# BrewDoo.net
KiCad netlist of a schematic drawn in EAGLE
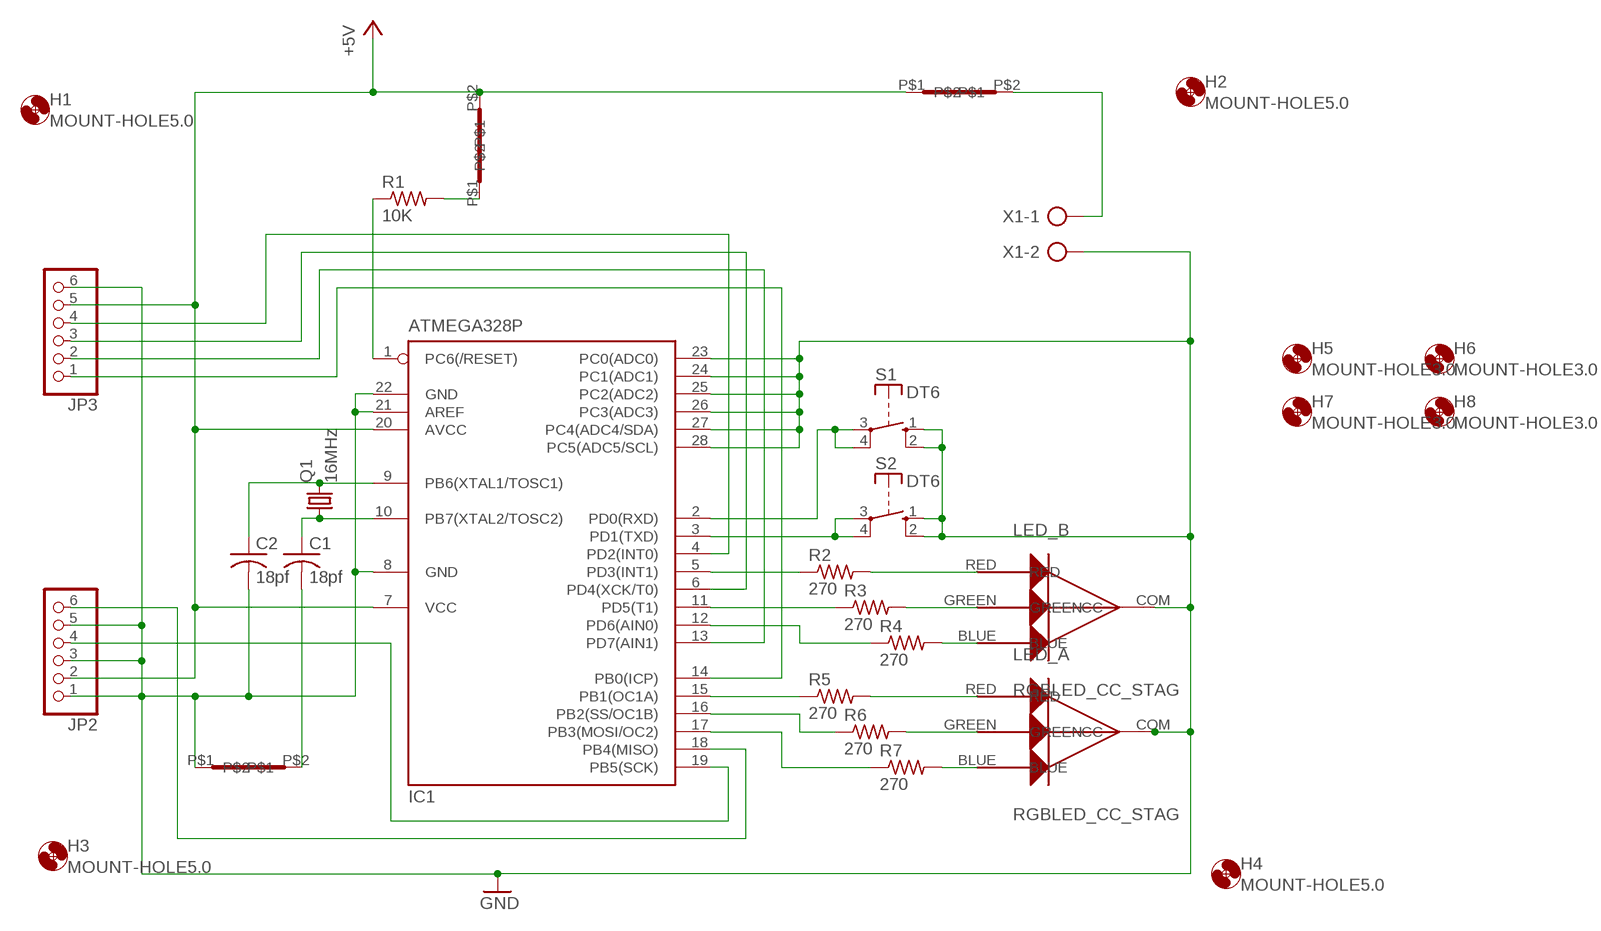
[diagram p0: schematic, sheet 1]

(export (version "E")
  (design (tool "Eeschema 10.0.6"))
  (components
    (comp (ref "C1")
      (value "18pf")
      (footprint "eagle-import:C025-025X050")
      (libsource (lib "eagle-import") (part "C-US025-025X050"))
    )
    (comp (ref "C2")
      (value "18pf")
      (footprint "eagle-import:C025-025X050")
      (libsource (lib "eagle-import") (part "C-US025-025X050"))
    )
    (comp (ref "H1")
      (value "MOUNT-HOLE5.0")
      (footprint "eagle-import:5,0")
      (libsource (lib "eagle-import") (part "MOUNT-HOLE5.0"))
    )
    (comp (ref "H2")
      (value "MOUNT-HOLE5.0")
      (footprint "eagle-import:5,0")
      (libsource (lib "eagle-import") (part "MOUNT-HOLE5.0"))
    )
    (comp (ref "H3")
      (value "MOUNT-HOLE5.0")
      (footprint "eagle-import:5,0")
      (libsource (lib "eagle-import") (part "MOUNT-HOLE5.0"))
    )
    (comp (ref "H4")
      (value "MOUNT-HOLE5.0")
      (footprint "eagle-import:5,0")
      (libsource (lib "eagle-import") (part "MOUNT-HOLE5.0"))
    )
    (comp (ref "H5")
      (value "MOUNT-HOLE3.0")
      (footprint "eagle-import:3,0")
      (libsource (lib "eagle-import") (part "MOUNT-HOLE3.0"))
    )
    (comp (ref "H6")
      (value "MOUNT-HOLE3.0")
      (footprint "eagle-import:3,0")
      (libsource (lib "eagle-import") (part "MOUNT-HOLE3.0"))
    )
    (comp (ref "H7")
      (value "MOUNT-HOLE3.0")
      (footprint "eagle-import:3,0")
      (libsource (lib "eagle-import") (part "MOUNT-HOLE3.0"))
    )
    (comp (ref "H8")
      (value "MOUNT-HOLE3.0")
      (footprint "eagle-import:3,0")
      (libsource (lib "eagle-import") (part "MOUNT-HOLE3.0"))
    )
    (comp (ref "IC1")
      (value "ATMEGA328P")
      (footprint "eagle-import:DIL28-3")
      (libsource (lib "eagle-import") (part "MEGA8-P"))
    )
    (comp (ref "JP2")
      (value "PINHD-1X6")
      (footprint "eagle-import:1X06")
      (libsource (lib "eagle-import") (part "PINHD-1X6"))
    )
    (comp (ref "JP3")
      (value "PINHD-1X6")
      (footprint "eagle-import:1X06")
      (libsource (lib "eagle-import") (part "PINHD-1X6"))
    )
    (comp (ref "LED_A")
      (value "RGBLED_CC_STAG")
      (footprint "eagle-import:RGBLED_STAGG")
      (libsource (lib "eagle-import") (part "RGBLED_CC_STAG"))
    )
    (comp (ref "LED_B")
      (value "RGBLED_CC_STAG")
      (footprint "eagle-import:RGBLED_STAGG")
      (libsource (lib "eagle-import") (part "RGBLED_CC_STAG"))
    )
    (comp (ref "Q1")
      (value "16MHz")
      (footprint "eagle-import:HC49_S")
      (libsource (lib "eagle-import") (part "CRYSTALHC49S"))
    )
    (comp (ref "R1")
      (value "10K")
      (footprint "eagle-import:0204_7")
      (libsource (lib "eagle-import") (part "R-US_0204/7"))
    )
    (comp (ref "R2")
      (value "270")
      (footprint "eagle-import:0207_12")
      (libsource (lib "eagle-import") (part "R-US_0207/12"))
    )
    (comp (ref "R3")
      (value "270")
      (footprint "eagle-import:0207_10")
      (libsource (lib "eagle-import") (part "R-US_0207/10"))
    )
    (comp (ref "R4")
      (value "270")
      (footprint "eagle-import:0207_10")
      (libsource (lib "eagle-import") (part "R-US_0207/10"))
    )
    (comp (ref "R5")
      (value "270")
      (footprint "eagle-import:0207_15")
      (libsource (lib "eagle-import") (part "R-US_0207/15"))
    )
    (comp (ref "R6")
      (value "270")
      (footprint "eagle-import:0207_15")
      (libsource (lib "eagle-import") (part "R-US_0207/15"))
    )
    (comp (ref "R7")
      (value "270")
      (footprint "eagle-import:0207_15")
      (libsource (lib "eagle-import") (part "R-US_0207/15"))
    )
    (comp (ref "S1")
      (value "DT6")
      (footprint "eagle-import:DT6")
      (libsource (lib "eagle-import") (part "DT6"))
    )
    (comp (ref "S2")
      (value "DT6")
      (footprint "eagle-import:DT6")
      (libsource (lib "eagle-import") (part "DT6"))
    )
    (comp (ref "U$1")
      (value "WIRE-0.3")
      (footprint "eagle-import:WIRE-0.3")
      (libsource (lib "eagle-import") (part "WIRE-0.3"))
    )
    (comp (ref "U$2")
      (value "WIRE-0.3")
      (footprint "eagle-import:WIRE-0.3")
      (libsource (lib "eagle-import") (part "WIRE-0.3"))
    )
    (comp (ref "U$3")
      (value "WIRE-0.6")
      (footprint "eagle-import:WIRE-0.6")
      (libsource (lib "eagle-import") (part "WIRE-0.6"))
    )
    (comp (ref "X1")
      (value "AK300/2")
      (footprint "eagle-import:AK300_2")
      (libsource (lib "eagle-import") (part "AK300/2"))
    )
  )
  (nets
    (net (code "1") (name "+5V") (class "Default")
      (node (ref "IC1") (pin "20") (pinfunction "AVCC_20") (pintype "power_in"))
      (node (ref "IC1") (pin "7") (pinfunction "VCC_7") (pintype "power_in"))
      (node (ref "JP2") (pin "2") (pinfunction "2_2") (pintype "passive"))
      (node (ref "JP3") (pin "5") (pinfunction "5_5") (pintype "passive"))
      (node (ref "R1") (pin "2") (pinfunction "2_2") (pintype "passive"))
      (node (ref "U$1") (pin "P$1") (pinfunction "P$1_P$1") (pintype "bidirectional"))
      (node (ref "U$1") (pin "P$2") (pinfunction "P$2_P$2") (pintype "bidirectional"))
      (node (ref "U$3") (pin "P$1") (pinfunction "P$1_P$1") (pintype "bidirectional"))
      (node (ref "U$3") (pin "P$2") (pinfunction "P$2_P$2") (pintype "bidirectional"))
      (node (ref "X1") (pin "1") (pinfunction "KL_1") (pintype "passive"))
    )
    (net (code "2") (name "GND") (class "Default")
      (node (ref "C1") (pin "2") (pinfunction "2_2") (pintype "passive"))
      (node (ref "C2") (pin "2") (pinfunction "2_2") (pintype "passive"))
      (node (ref "IC1") (pin "21") (pinfunction "AREF_21") (pintype "passive"))
      (node (ref "IC1") (pin "22") (pinfunction "GND_22") (pintype "power_in"))
      (node (ref "IC1") (pin "23") (pinfunction "PC0(ADC0)_23") (pintype "bidirectional"))
      (node (ref "IC1") (pin "24") (pinfunction "PC1(ADC1)_24") (pintype "bidirectional"))
      (node (ref "IC1") (pin "25") (pinfunction "PC2(ADC2)_25") (pintype "bidirectional"))
      (node (ref "IC1") (pin "26") (pinfunction "PC3(ADC3)_26") (pintype "bidirectional"))
      (node (ref "IC1") (pin "27") (pinfunction "PC4(ADC4/SDA)_27") (pintype "bidirectional"))
      (node (ref "IC1") (pin "28") (pinfunction "PC5(ADC5/SCL)_28") (pintype "bidirectional"))
      (node (ref "IC1") (pin "8") (pinfunction "GND_8") (pintype "power_in"))
      (node (ref "JP2") (pin "1") (pinfunction "1_1") (pintype "passive"))
      (node (ref "JP2") (pin "3") (pinfunction "3_3") (pintype "passive"))
      (node (ref "JP2") (pin "5") (pinfunction "5_5") (pintype "passive"))
      (node (ref "JP3") (pin "6") (pinfunction "6_6") (pintype "passive"))
      (node (ref "LED_A") (pin "COM") (pinfunction "CC_COM") (pintype "bidirectional"))
      (node (ref "LED_B") (pin "COM") (pinfunction "CC_COM") (pintype "bidirectional"))
      (node (ref "S1") (pin "1") (pinfunction "S_1") (pintype "passive"))
      (node (ref "S1") (pin "2") (pinfunction "S_2") (pintype "passive"))
      (node (ref "S2") (pin "1") (pinfunction "S_1") (pintype "passive"))
      (node (ref "S2") (pin "2") (pinfunction "S_2") (pintype "passive"))
      (node (ref "U$2") (pin "P$1") (pinfunction "P$1_P$1") (pintype "bidirectional"))
      (node (ref "U$2") (pin "P$2") (pinfunction "P$2_P$2") (pintype "bidirectional"))
      (node (ref "X1") (pin "2") (pinfunction "KL_2") (pintype "passive"))
    )
    (net (code "3") (name "Net-(IC1-PB0(ICP))") (class "Default")
      (node (ref "IC1") (pin "14") (pinfunction "PB0(ICP)_14") (pintype "bidirectional"))
      (node (ref "JP3") (pin "1") (pinfunction "1_1") (pintype "passive"))
    )
    (net (code "4") (name "Net-(IC1-PB1(OC1A))") (class "Default")
      (node (ref "IC1") (pin "15") (pinfunction "PB1(OC1A)_15") (pintype "bidirectional"))
      (node (ref "R5") (pin "1") (pinfunction "1_1") (pintype "passive"))
    )
    (net (code "5") (name "Net-(IC1-PB2(SS{slash}OC1B))") (class "Default")
      (node (ref "IC1") (pin "16") (pinfunction "PB2(SS/OC1B)_16") (pintype "bidirectional"))
      (node (ref "R6") (pin "1") (pinfunction "1_1") (pintype "passive"))
    )
    (net (code "6") (name "Net-(IC1-PB3(MOSI{slash}OC2))") (class "Default")
      (node (ref "IC1") (pin "17") (pinfunction "PB3(MOSI/OC2)_17") (pintype "bidirectional"))
      (node (ref "R7") (pin "1") (pinfunction "1_1") (pintype "passive"))
    )
    (net (code "7") (name "Net-(IC1-PB4(MISO))") (class "Default")
      (node (ref "IC1") (pin "18") (pinfunction "PB4(MISO)_18") (pintype "bidirectional"))
      (node (ref "JP2") (pin "6") (pinfunction "6_6") (pintype "passive"))
    )
    (net (code "8") (name "Net-(IC1-PB5(SCK))") (class "Default")
      (node (ref "IC1") (pin "19") (pinfunction "PB5(SCK)_19") (pintype "bidirectional"))
      (node (ref "JP2") (pin "4") (pinfunction "4_4") (pintype "passive"))
    )
    (net (code "9") (name "Net-(IC1-PB6(XTAL1{slash}TOSC1))") (class "Default")
      (node (ref "C2") (pin "1") (pinfunction "1_1") (pintype "passive"))
      (node (ref "IC1") (pin "9") (pinfunction "PB6(XTAL1/TOSC1)_9") (pintype "bidirectional"))
      (node (ref "Q1") (pin "2") (pinfunction "2_2") (pintype "passive"))
    )
    (net (code "10") (name "Net-(IC1-PB7(XTAL2{slash}TOSC2))") (class "Default")
      (node (ref "C1") (pin "1") (pinfunction "1_1") (pintype "passive"))
      (node (ref "IC1") (pin "10") (pinfunction "PB7(XTAL2/TOSC2)_10") (pintype "bidirectional"))
      (node (ref "Q1") (pin "1") (pinfunction "1_1") (pintype "passive"))
    )
    (net (code "11") (name "Net-(IC1-PC6({slash}RESET))") (class "Default")
      (node (ref "IC1") (pin "1") (pinfunction "PC6(/RESET)_1") (pintype "bidirectional"))
      (node (ref "R1") (pin "1") (pinfunction "1_1") (pintype "passive"))
    )
    (net (code "12") (name "Net-(IC1-PD0(RXD))") (class "Default")
      (node (ref "IC1") (pin "2") (pinfunction "PD0(RXD)_2") (pintype "bidirectional"))
      (node (ref "S1") (pin "3") (pinfunction "P_3") (pintype "passive"))
      (node (ref "S1") (pin "4") (pinfunction "P_4") (pintype "passive"))
    )
    (net (code "13") (name "Net-(IC1-PD1(TXD))") (class "Default")
      (node (ref "IC1") (pin "3") (pinfunction "PD1(TXD)_3") (pintype "bidirectional"))
      (node (ref "S2") (pin "3") (pinfunction "P_3") (pintype "passive"))
      (node (ref "S2") (pin "4") (pinfunction "P_4") (pintype "passive"))
    )
    (net (code "14") (name "Net-(IC1-PD2(INT0))") (class "Default")
      (node (ref "IC1") (pin "4") (pinfunction "PD2(INT0)_4") (pintype "bidirectional"))
      (node (ref "JP3") (pin "4") (pinfunction "4_4") (pintype "passive"))
    )
    (net (code "15") (name "Net-(IC1-PD3(INT1))") (class "Default")
      (node (ref "IC1") (pin "5") (pinfunction "PD3(INT1)_5") (pintype "bidirectional"))
      (node (ref "R2") (pin "1") (pinfunction "1_1") (pintype "passive"))
    )
    (net (code "16") (name "Net-(IC1-PD4(XCK{slash}T0))") (class "Default")
      (node (ref "IC1") (pin "6") (pinfunction "PD4(XCK/T0)_6") (pintype "bidirectional"))
      (node (ref "JP3") (pin "3") (pinfunction "3_3") (pintype "passive"))
    )
    (net (code "17") (name "Net-(IC1-PD5(T1))") (class "Default")
      (node (ref "IC1") (pin "11") (pinfunction "PD5(T1)_11") (pintype "bidirectional"))
      (node (ref "R3") (pin "1") (pinfunction "1_1") (pintype "passive"))
    )
    (net (code "18") (name "Net-(IC1-PD6(AIN0))") (class "Default")
      (node (ref "IC1") (pin "12") (pinfunction "PD6(AIN0)_12") (pintype "bidirectional"))
      (node (ref "R4") (pin "1") (pinfunction "1_1") (pintype "passive"))
    )
    (net (code "19") (name "Net-(IC1-PD7(AIN1))") (class "Default")
      (node (ref "IC1") (pin "13") (pinfunction "PD7(AIN1)_13") (pintype "bidirectional"))
      (node (ref "JP3") (pin "2") (pinfunction "2_2") (pintype "passive"))
    )
    (net (code "20") (name "Net-(LED_A-PadBLUE)") (class "Default")
      (node (ref "LED_A") (pin "BLUE") (pinfunction "BLUE_BLUE") (pintype "bidirectional"))
      (node (ref "R7") (pin "2") (pinfunction "2_2") (pintype "passive"))
    )
    (net (code "21") (name "Net-(LED_A-PadGREEN)") (class "Default")
      (node (ref "LED_A") (pin "GREEN") (pinfunction "GREEN_GREEN") (pintype "bidirectional"))
      (node (ref "R6") (pin "2") (pinfunction "2_2") (pintype "passive"))
    )
    (net (code "22") (name "Net-(LED_A-PadRED)") (class "Default")
      (node (ref "LED_A") (pin "RED") (pinfunction "RED_RED") (pintype "bidirectional"))
      (node (ref "R5") (pin "2") (pinfunction "2_2") (pintype "passive"))
    )
    (net (code "23") (name "Net-(LED_B-PadBLUE)") (class "Default")
      (node (ref "LED_B") (pin "BLUE") (pinfunction "BLUE_BLUE") (pintype "bidirectional"))
      (node (ref "R4") (pin "2") (pinfunction "2_2") (pintype "passive"))
    )
    (net (code "24") (name "Net-(LED_B-PadGREEN)") (class "Default")
      (node (ref "LED_B") (pin "GREEN") (pinfunction "GREEN_GREEN") (pintype "bidirectional"))
      (node (ref "R3") (pin "2") (pinfunction "2_2") (pintype "passive"))
    )
    (net (code "25") (name "Net-(LED_B-PadRED)") (class "Default")
      (node (ref "LED_B") (pin "RED") (pinfunction "RED_RED") (pintype "bidirectional"))
      (node (ref "R2") (pin "2") (pinfunction "2_2") (pintype "passive"))
    )
  )
)
